# cockpitV3-_XPDNR-_support_mega_2560_2021.net
KiCad netlist of a schematic drawn in EasyEDA
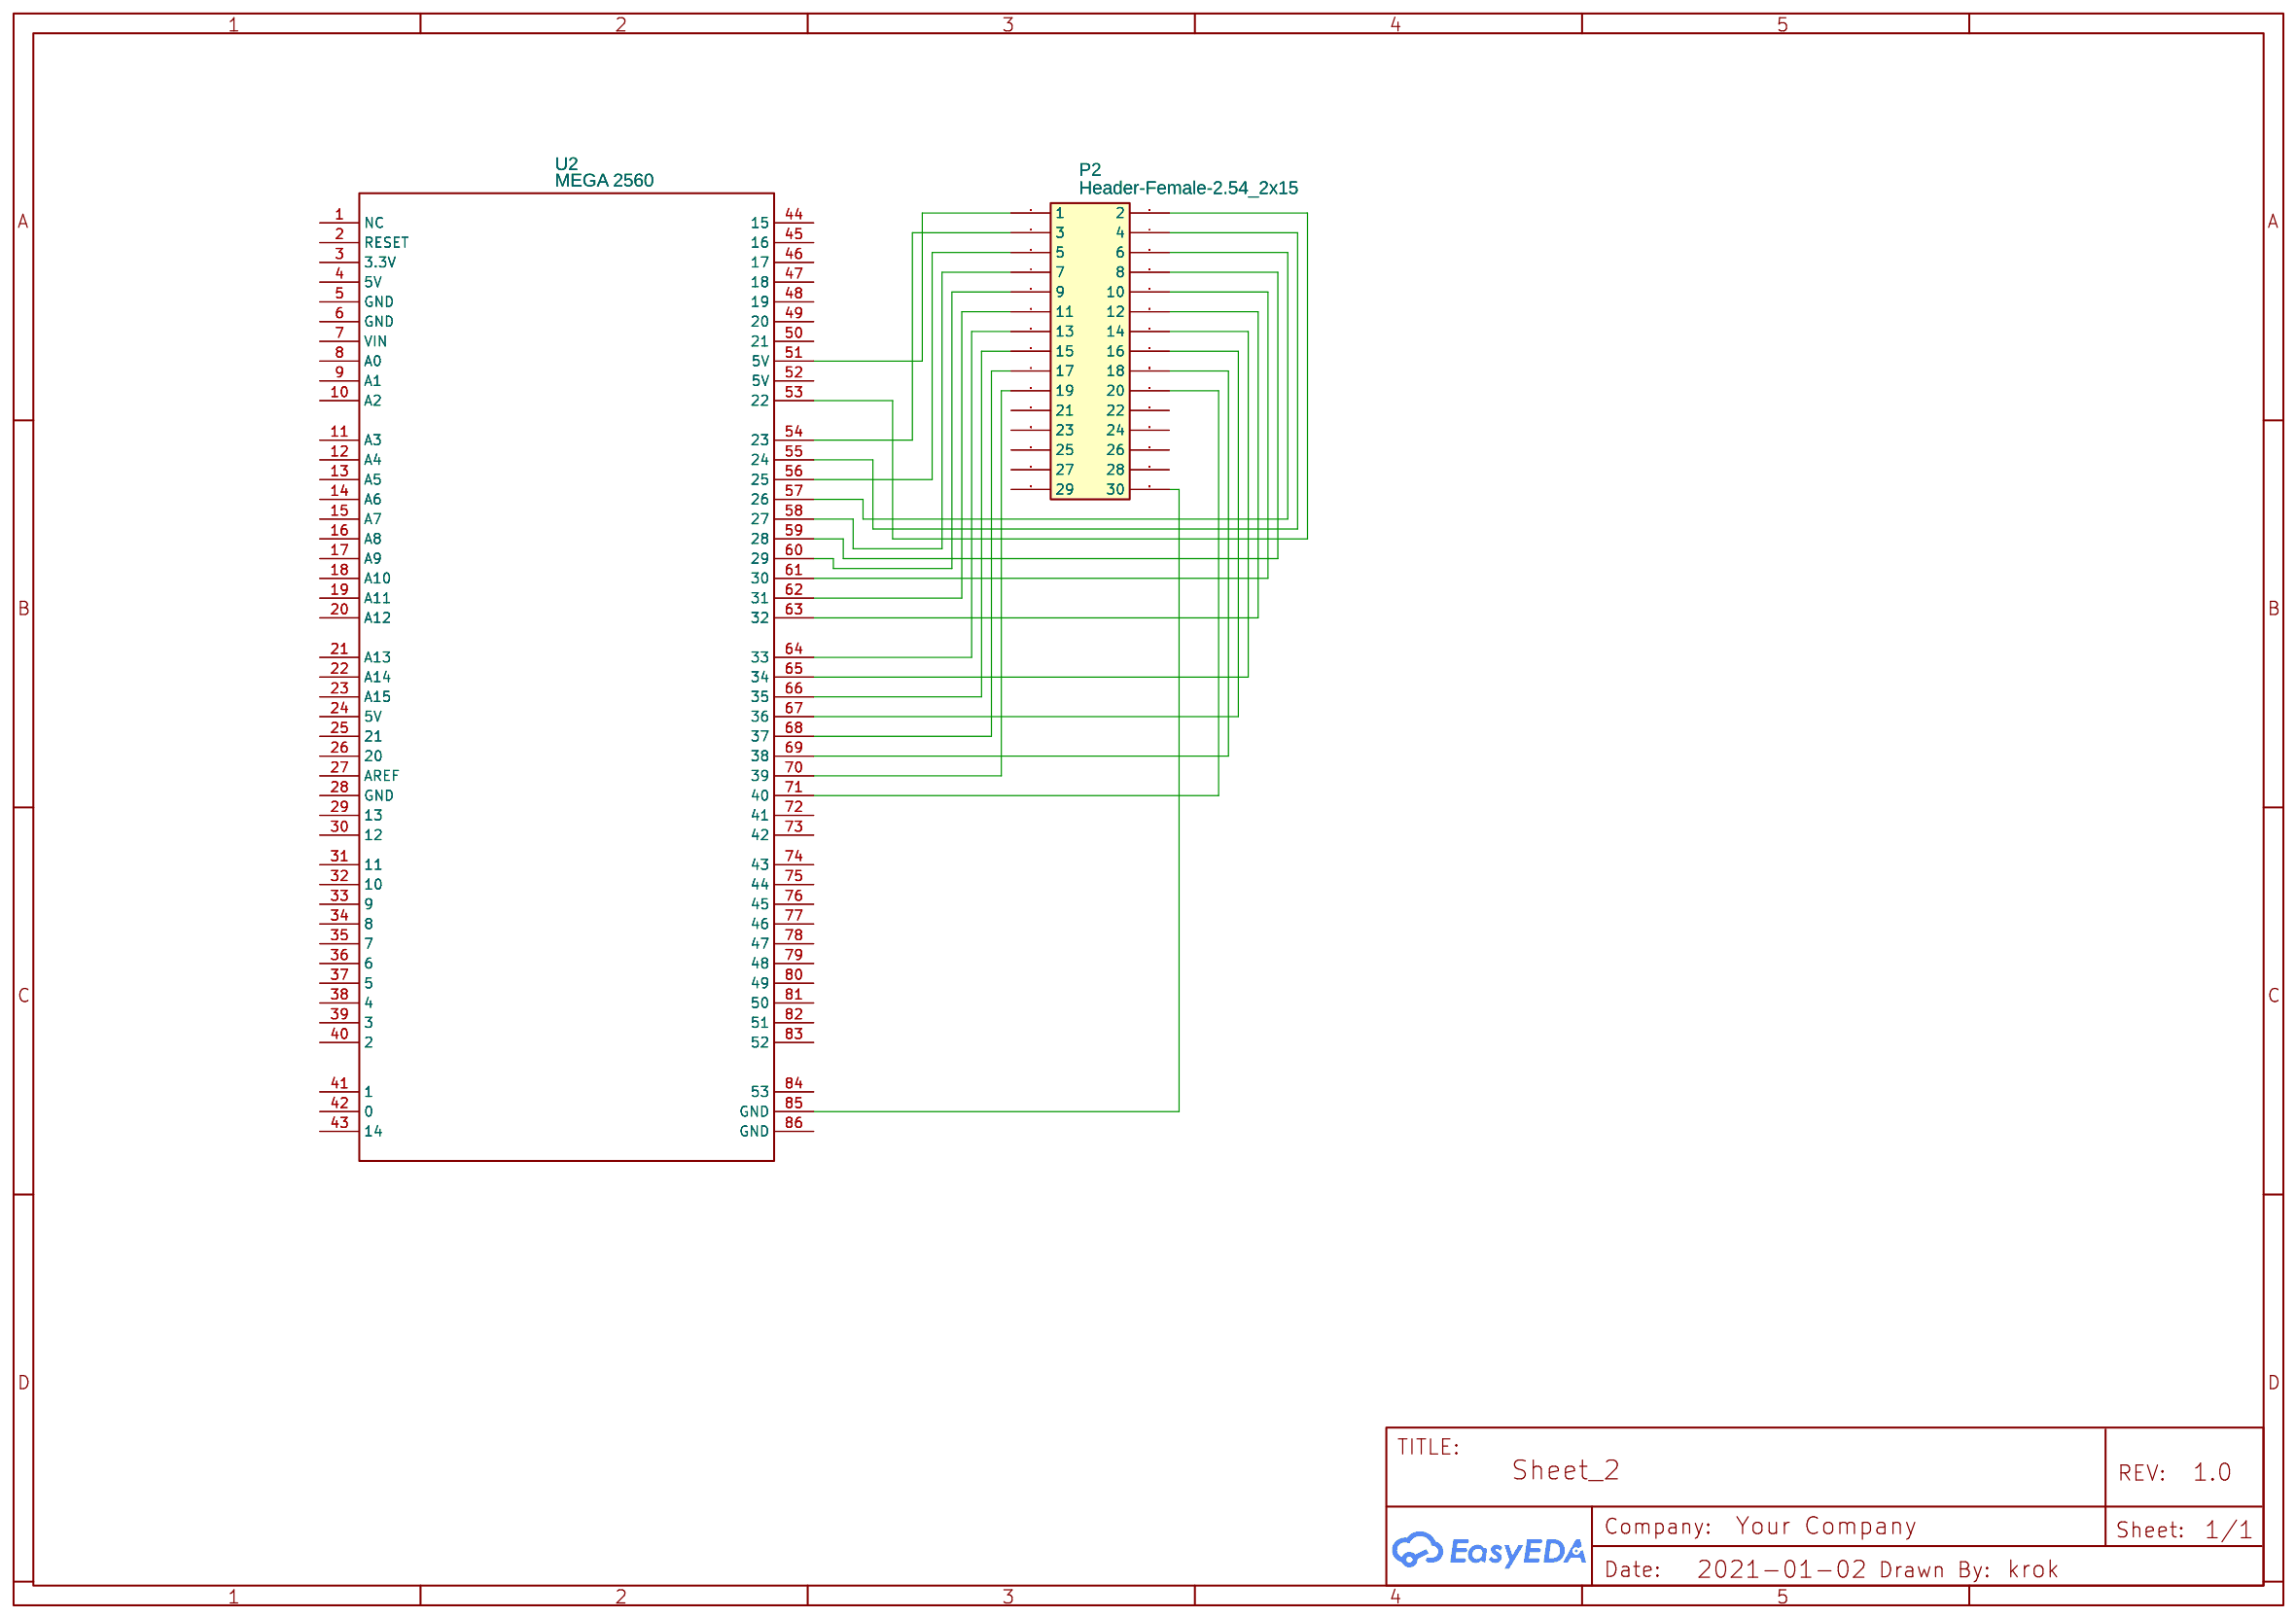
[diagram p0: schematic sheet]

(export (version "E")
  (design (tool "Eeschema 10.0.6"))
  (components
    (comp (ref "P2")
      (value "Header-Female-2.54_2x15")
      (fields (field (name "BOM_Supplier Part") "E58377"))
      (libsource (lib "") (part "Header-Female-2.54_2x15"))
    )
    (comp (ref "U2") (value "MEGA 2560") (libsource (lib "") (part "MEGA 2560")))
  )
  (nets
    (net (code "1") (name "Net-(P2-Pad1)") (class "Default")
      (node (ref "P2") (pin "1") (pinfunction "1_1") (pintype "input"))
      (node (ref "U2") (pin "51") (pinfunction "5V_51") (pintype "unspecified"))
    )
    (net (code "2") (name "Net-(P2-Pad30)") (class "Default")
      (node (ref "P2") (pin "30") (pinfunction "30_30") (pintype "input"))
      (node (ref "U2") (pin "85") (pinfunction "GND_85") (pintype "unspecified"))
    )
    (net (code "3") (name "Net-(U2-22)") (class "Default")
      (node (ref "P2") (pin "2") (pinfunction "2_2") (pintype "input"))
      (node (ref "U2") (pin "53") (pinfunction "22_53") (pintype "unspecified"))
    )
    (net (code "4") (name "Net-(U2-23)") (class "Default")
      (node (ref "P2") (pin "3") (pinfunction "3_3") (pintype "input"))
      (node (ref "U2") (pin "54") (pinfunction "23_54") (pintype "unspecified"))
    )
    (net (code "5") (name "Net-(U2-24)") (class "Default")
      (node (ref "P2") (pin "4") (pinfunction "4_4") (pintype "input"))
      (node (ref "U2") (pin "55") (pinfunction "24_55") (pintype "unspecified"))
    )
    (net (code "6") (name "Net-(U2-25)") (class "Default")
      (node (ref "P2") (pin "5") (pinfunction "5_5") (pintype "input"))
      (node (ref "U2") (pin "56") (pinfunction "25_56") (pintype "unspecified"))
    )
    (net (code "7") (name "Net-(U2-26)") (class "Default")
      (node (ref "P2") (pin "6") (pinfunction "6_6") (pintype "input"))
      (node (ref "U2") (pin "57") (pinfunction "26_57") (pintype "unspecified"))
    )
    (net (code "8") (name "Net-(U2-27)") (class "Default")
      (node (ref "P2") (pin "7") (pinfunction "7_7") (pintype "input"))
      (node (ref "U2") (pin "58") (pinfunction "27_58") (pintype "unspecified"))
    )
    (net (code "9") (name "Net-(U2-28)") (class "Default")
      (node (ref "P2") (pin "8") (pinfunction "8_8") (pintype "input"))
      (node (ref "U2") (pin "59") (pinfunction "28_59") (pintype "unspecified"))
    )
    (net (code "10") (name "Net-(U2-29)") (class "Default")
      (node (ref "P2") (pin "9") (pinfunction "9_9") (pintype "input"))
      (node (ref "U2") (pin "60") (pinfunction "29_60") (pintype "unspecified"))
    )
    (net (code "11") (name "Net-(U2-30)") (class "Default")
      (node (ref "P2") (pin "10") (pinfunction "10_10") (pintype "input"))
      (node (ref "U2") (pin "61") (pinfunction "30_61") (pintype "unspecified"))
    )
    (net (code "12") (name "Net-(U2-31)") (class "Default")
      (node (ref "P2") (pin "11") (pinfunction "11_11") (pintype "input"))
      (node (ref "U2") (pin "62") (pinfunction "31_62") (pintype "unspecified"))
    )
    (net (code "13") (name "Net-(U2-32)") (class "Default")
      (node (ref "P2") (pin "12") (pinfunction "12_12") (pintype "input"))
      (node (ref "U2") (pin "63") (pinfunction "32_63") (pintype "unspecified"))
    )
    (net (code "14") (name "Net-(U2-33)") (class "Default")
      (node (ref "P2") (pin "13") (pinfunction "13_13") (pintype "input"))
      (node (ref "U2") (pin "64") (pinfunction "33_64") (pintype "unspecified"))
    )
    (net (code "15") (name "Net-(U2-34)") (class "Default")
      (node (ref "P2") (pin "14") (pinfunction "14_14") (pintype "input"))
      (node (ref "U2") (pin "65") (pinfunction "34_65") (pintype "unspecified"))
    )
    (net (code "16") (name "Net-(U2-35)") (class "Default")
      (node (ref "P2") (pin "15") (pinfunction "15_15") (pintype "input"))
      (node (ref "U2") (pin "66") (pinfunction "35_66") (pintype "unspecified"))
    )
    (net (code "17") (name "Net-(U2-36)") (class "Default")
      (node (ref "P2") (pin "16") (pinfunction "16_16") (pintype "input"))
      (node (ref "U2") (pin "67") (pinfunction "36_67") (pintype "unspecified"))
    )
    (net (code "18") (name "Net-(U2-37)") (class "Default")
      (node (ref "P2") (pin "17") (pinfunction "17_17") (pintype "input"))
      (node (ref "U2") (pin "68") (pinfunction "37_68") (pintype "unspecified"))
    )
    (net (code "19") (name "Net-(U2-38)") (class "Default")
      (node (ref "P2") (pin "18") (pinfunction "18_18") (pintype "input"))
      (node (ref "U2") (pin "69") (pinfunction "38_69") (pintype "unspecified"))
    )
    (net (code "20") (name "Net-(U2-39)") (class "Default")
      (node (ref "P2") (pin "19") (pinfunction "19_19") (pintype "input"))
      (node (ref "U2") (pin "70") (pinfunction "39_70") (pintype "unspecified"))
    )
    (net (code "21") (name "Net-(U2-40)") (class "Default")
      (node (ref "P2") (pin "20") (pinfunction "20_20") (pintype "input"))
      (node (ref "U2") (pin "71") (pinfunction "40_71") (pintype "unspecified"))
    )
    (net (code "22") (name "unconnected-(P2-Pad21)") (class "Default")
      (node (ref "P2") (pin "21") (pinfunction "21_21") (pintype "input"))
    )
    (net (code "23") (name "unconnected-(P2-Pad22)") (class "Default")
      (node (ref "P2") (pin "22") (pinfunction "22_22") (pintype "input"))
    )
    (net (code "24") (name "unconnected-(P2-Pad23)") (class "Default")
      (node (ref "P2") (pin "23") (pinfunction "23_23") (pintype "input"))
    )
    (net (code "25") (name "unconnected-(P2-Pad24)") (class "Default")
      (node (ref "P2") (pin "24") (pinfunction "24_24") (pintype "input"))
    )
    (net (code "26") (name "unconnected-(P2-Pad25)") (class "Default")
      (node (ref "P2") (pin "25") (pinfunction "25_25") (pintype "input"))
    )
    (net (code "27") (name "unconnected-(P2-Pad26)") (class "Default")
      (node (ref "P2") (pin "26") (pinfunction "26_26") (pintype "input"))
    )
    (net (code "28") (name "unconnected-(P2-Pad27)") (class "Default")
      (node (ref "P2") (pin "27") (pinfunction "27_27") (pintype "input"))
    )
    (net (code "29") (name "unconnected-(P2-Pad28)") (class "Default")
      (node (ref "P2") (pin "28") (pinfunction "28_28") (pintype "input"))
    )
    (net (code "30") (name "unconnected-(P2-Pad29)") (class "Default")
      (node (ref "P2") (pin "29") (pinfunction "29_29") (pintype "input"))
    )
    (net (code "31") (name "unconnected-(U2-0-Pad42)") (class "Default")
      (node (ref "U2") (pin "42") (pinfunction "0_42") (pintype "unspecified"))
    )
    (net (code "32") (name "unconnected-(U2-1-Pad41)") (class "Default")
      (node (ref "U2") (pin "41") (pinfunction "1_41") (pintype "unspecified"))
    )
    (net (code "33") (name "unconnected-(U2-2-Pad40)") (class "Default")
      (node (ref "U2") (pin "40") (pinfunction "2_40") (pintype "unspecified"))
    )
    (net (code "34") (name "unconnected-(U2-3-Pad39)") (class "Default")
      (node (ref "U2") (pin "39") (pinfunction "3_39") (pintype "unspecified"))
    )
    (net (code "35") (name "unconnected-(U2-3.3V-Pad3)") (class "Default")
      (node (ref "U2") (pin "3") (pinfunction "3.3V_3") (pintype "unspecified"))
    )
    (net (code "36") (name "unconnected-(U2-4-Pad38)") (class "Default")
      (node (ref "U2") (pin "38") (pinfunction "4_38") (pintype "unspecified"))
    )
    (net (code "37") (name "unconnected-(U2-5-Pad37)") (class "Default")
      (node (ref "U2") (pin "37") (pinfunction "5_37") (pintype "unspecified"))
    )
    (net (code "38") (name "unconnected-(U2-5V-Pad4)") (class "Default")
      (node (ref "U2") (pin "4") (pinfunction "5V_4") (pintype "unspecified"))
    )
    (net (code "39") (name "unconnected-(U2-5V-Pad24)") (class "Default")
      (node (ref "U2") (pin "24") (pinfunction "5V_24") (pintype "unspecified"))
    )
    (net (code "40") (name "unconnected-(U2-5V-Pad52)") (class "Default")
      (node (ref "U2") (pin "52") (pinfunction "5V_52") (pintype "unspecified"))
    )
    (net (code "41") (name "unconnected-(U2-6-Pad36)") (class "Default")
      (node (ref "U2") (pin "36") (pinfunction "6_36") (pintype "unspecified"))
    )
    (net (code "42") (name "unconnected-(U2-7-Pad35)") (class "Default")
      (node (ref "U2") (pin "35") (pinfunction "7_35") (pintype "unspecified"))
    )
    (net (code "43") (name "unconnected-(U2-8-Pad34)") (class "Default")
      (node (ref "U2") (pin "34") (pinfunction "8_34") (pintype "unspecified"))
    )
    (net (code "44") (name "unconnected-(U2-9-Pad33)") (class "Default")
      (node (ref "U2") (pin "33") (pinfunction "9_33") (pintype "unspecified"))
    )
    (net (code "45") (name "unconnected-(U2-10-Pad32)") (class "Default")
      (node (ref "U2") (pin "32") (pinfunction "10_32") (pintype "unspecified"))
    )
    (net (code "46") (name "unconnected-(U2-11-Pad31)") (class "Default")
      (node (ref "U2") (pin "31") (pinfunction "11_31") (pintype "unspecified"))
    )
    (net (code "47") (name "unconnected-(U2-12-Pad30)") (class "Default")
      (node (ref "U2") (pin "30") (pinfunction "12_30") (pintype "unspecified"))
    )
    (net (code "48") (name "unconnected-(U2-13-Pad29)") (class "Default")
      (node (ref "U2") (pin "29") (pinfunction "13_29") (pintype "unspecified"))
    )
    (net (code "49") (name "unconnected-(U2-14-Pad43)") (class "Default")
      (node (ref "U2") (pin "43") (pinfunction "14_43") (pintype "unspecified"))
    )
    (net (code "50") (name "unconnected-(U2-15-Pad44)") (class "Default")
      (node (ref "U2") (pin "44") (pinfunction "15_44") (pintype "unspecified"))
    )
    (net (code "51") (name "unconnected-(U2-16-Pad45)") (class "Default")
      (node (ref "U2") (pin "45") (pinfunction "16_45") (pintype "unspecified"))
    )
    (net (code "52") (name "unconnected-(U2-17-Pad46)") (class "Default")
      (node (ref "U2") (pin "46") (pinfunction "17_46") (pintype "unspecified"))
    )
    (net (code "53") (name "unconnected-(U2-18-Pad47)") (class "Default")
      (node (ref "U2") (pin "47") (pinfunction "18_47") (pintype "unspecified"))
    )
    (net (code "54") (name "unconnected-(U2-19-Pad48)") (class "Default")
      (node (ref "U2") (pin "48") (pinfunction "19_48") (pintype "unspecified"))
    )
    (net (code "55") (name "unconnected-(U2-20-Pad26)") (class "Default")
      (node (ref "U2") (pin "26") (pinfunction "20_26") (pintype "unspecified"))
    )
    (net (code "56") (name "unconnected-(U2-20-Pad49)") (class "Default")
      (node (ref "U2") (pin "49") (pinfunction "20_49") (pintype "unspecified"))
    )
    (net (code "57") (name "unconnected-(U2-21-Pad25)") (class "Default")
      (node (ref "U2") (pin "25") (pinfunction "21_25") (pintype "unspecified"))
    )
    (net (code "58") (name "unconnected-(U2-21-Pad50)") (class "Default")
      (node (ref "U2") (pin "50") (pinfunction "21_50") (pintype "unspecified"))
    )
    (net (code "59") (name "unconnected-(U2-41-Pad72)") (class "Default")
      (node (ref "U2") (pin "72") (pinfunction "41_72") (pintype "unspecified"))
    )
    (net (code "60") (name "unconnected-(U2-42-Pad73)") (class "Default")
      (node (ref "U2") (pin "73") (pinfunction "42_73") (pintype "unspecified"))
    )
    (net (code "61") (name "unconnected-(U2-43-Pad74)") (class "Default")
      (node (ref "U2") (pin "74") (pinfunction "43_74") (pintype "unspecified"))
    )
    (net (code "62") (name "unconnected-(U2-44-Pad75)") (class "Default")
      (node (ref "U2") (pin "75") (pinfunction "44_75") (pintype "unspecified"))
    )
    (net (code "63") (name "unconnected-(U2-45-Pad76)") (class "Default")
      (node (ref "U2") (pin "76") (pinfunction "45_76") (pintype "unspecified"))
    )
    (net (code "64") (name "unconnected-(U2-46-Pad77)") (class "Default")
      (node (ref "U2") (pin "77") (pinfunction "46_77") (pintype "unspecified"))
    )
    (net (code "65") (name "unconnected-(U2-47-Pad78)") (class "Default")
      (node (ref "U2") (pin "78") (pinfunction "47_78") (pintype "unspecified"))
    )
    (net (code "66") (name "unconnected-(U2-48-Pad79)") (class "Default")
      (node (ref "U2") (pin "79") (pinfunction "48_79") (pintype "unspecified"))
    )
    (net (code "67") (name "unconnected-(U2-49-Pad80)") (class "Default")
      (node (ref "U2") (pin "80") (pinfunction "49_80") (pintype "unspecified"))
    )
    (net (code "68") (name "unconnected-(U2-50-Pad81)") (class "Default")
      (node (ref "U2") (pin "81") (pinfunction "50_81") (pintype "unspecified"))
    )
    (net (code "69") (name "unconnected-(U2-51-Pad82)") (class "Default")
      (node (ref "U2") (pin "82") (pinfunction "51_82") (pintype "unspecified"))
    )
    (net (code "70") (name "unconnected-(U2-52-Pad83)") (class "Default")
      (node (ref "U2") (pin "83") (pinfunction "52_83") (pintype "unspecified"))
    )
    (net (code "71") (name "unconnected-(U2-53-Pad84)") (class "Default")
      (node (ref "U2") (pin "84") (pinfunction "53_84") (pintype "unspecified"))
    )
    (net (code "72") (name "unconnected-(U2-A0-Pad8)") (class "Default")
      (node (ref "U2") (pin "8") (pinfunction "A0_8") (pintype "unspecified"))
    )
    (net (code "73") (name "unconnected-(U2-A1-Pad9)") (class "Default")
      (node (ref "U2") (pin "9") (pinfunction "A1_9") (pintype "unspecified"))
    )
    (net (code "74") (name "unconnected-(U2-A2-Pad10)") (class "Default")
      (node (ref "U2") (pin "10") (pinfunction "A2_10") (pintype "unspecified"))
    )
    (net (code "75") (name "unconnected-(U2-A3-Pad11)") (class "Default")
      (node (ref "U2") (pin "11") (pinfunction "A3_11") (pintype "unspecified"))
    )
    (net (code "76") (name "unconnected-(U2-A4-Pad12)") (class "Default")
      (node (ref "U2") (pin "12") (pinfunction "A4_12") (pintype "unspecified"))
    )
    (net (code "77") (name "unconnected-(U2-A5-Pad13)") (class "Default")
      (node (ref "U2") (pin "13") (pinfunction "A5_13") (pintype "unspecified"))
    )
    (net (code "78") (name "unconnected-(U2-A6-Pad14)") (class "Default")
      (node (ref "U2") (pin "14") (pinfunction "A6_14") (pintype "unspecified"))
    )
    (net (code "79") (name "unconnected-(U2-A7-Pad15)") (class "Default")
      (node (ref "U2") (pin "15") (pinfunction "A7_15") (pintype "unspecified"))
    )
    (net (code "80") (name "unconnected-(U2-A8-Pad16)") (class "Default")
      (node (ref "U2") (pin "16") (pinfunction "A8_16") (pintype "unspecified"))
    )
    (net (code "81") (name "unconnected-(U2-A9-Pad17)") (class "Default")
      (node (ref "U2") (pin "17") (pinfunction "A9_17") (pintype "unspecified"))
    )
    (net (code "82") (name "unconnected-(U2-A10-Pad18)") (class "Default")
      (node (ref "U2") (pin "18") (pinfunction "A10_18") (pintype "unspecified"))
    )
    (net (code "83") (name "unconnected-(U2-A11-Pad19)") (class "Default")
      (node (ref "U2") (pin "19") (pinfunction "A11_19") (pintype "unspecified"))
    )
    (net (code "84") (name "unconnected-(U2-A12-Pad20)") (class "Default")
      (node (ref "U2") (pin "20") (pinfunction "A12_20") (pintype "unspecified"))
    )
    (net (code "85") (name "unconnected-(U2-A13-Pad21)") (class "Default")
      (node (ref "U2") (pin "21") (pinfunction "A13_21") (pintype "unspecified"))
    )
    (net (code "86") (name "unconnected-(U2-A14-Pad22)") (class "Default")
      (node (ref "U2") (pin "22") (pinfunction "A14_22") (pintype "unspecified"))
    )
    (net (code "87") (name "unconnected-(U2-A15-Pad23)") (class "Default")
      (node (ref "U2") (pin "23") (pinfunction "A15_23") (pintype "unspecified"))
    )
    (net (code "88") (name "unconnected-(U2-AREF-Pad27)") (class "Default")
      (node (ref "U2") (pin "27") (pinfunction "AREF_27") (pintype "unspecified"))
    )
    (net (code "89") (name "unconnected-(U2-GND-Pad5)") (class "Default")
      (node (ref "U2") (pin "5") (pinfunction "GND_5") (pintype "unspecified"))
    )
    (net (code "90") (name "unconnected-(U2-GND-Pad6)") (class "Default")
      (node (ref "U2") (pin "6") (pinfunction "GND_6") (pintype "unspecified"))
    )
    (net (code "91") (name "unconnected-(U2-GND-Pad28)") (class "Default")
      (node (ref "U2") (pin "28") (pinfunction "GND_28") (pintype "unspecified"))
    )
    (net (code "92") (name "unconnected-(U2-GND-Pad86)") (class "Default")
      (node (ref "U2") (pin "86") (pinfunction "GND_86") (pintype "unspecified"))
    )
    (net (code "93") (name "unconnected-(U2-NC-Pad1)") (class "Default")
      (node (ref "U2") (pin "1") (pinfunction "NC_1") (pintype "unspecified"))
    )
    (net (code "94") (name "unconnected-(U2-RESET-Pad2)") (class "Default")
      (node (ref "U2") (pin "2") (pinfunction "RESET_2") (pintype "unspecified"))
    )
    (net (code "95") (name "unconnected-(U2-VIN-Pad7)") (class "Default")
      (node (ref "U2") (pin "7") (pinfunction "VIN_7") (pintype "unspecified"))
    )
  )
)
